# sb6pads.net
KiCad netlist of a schematic drawn in EAGLE
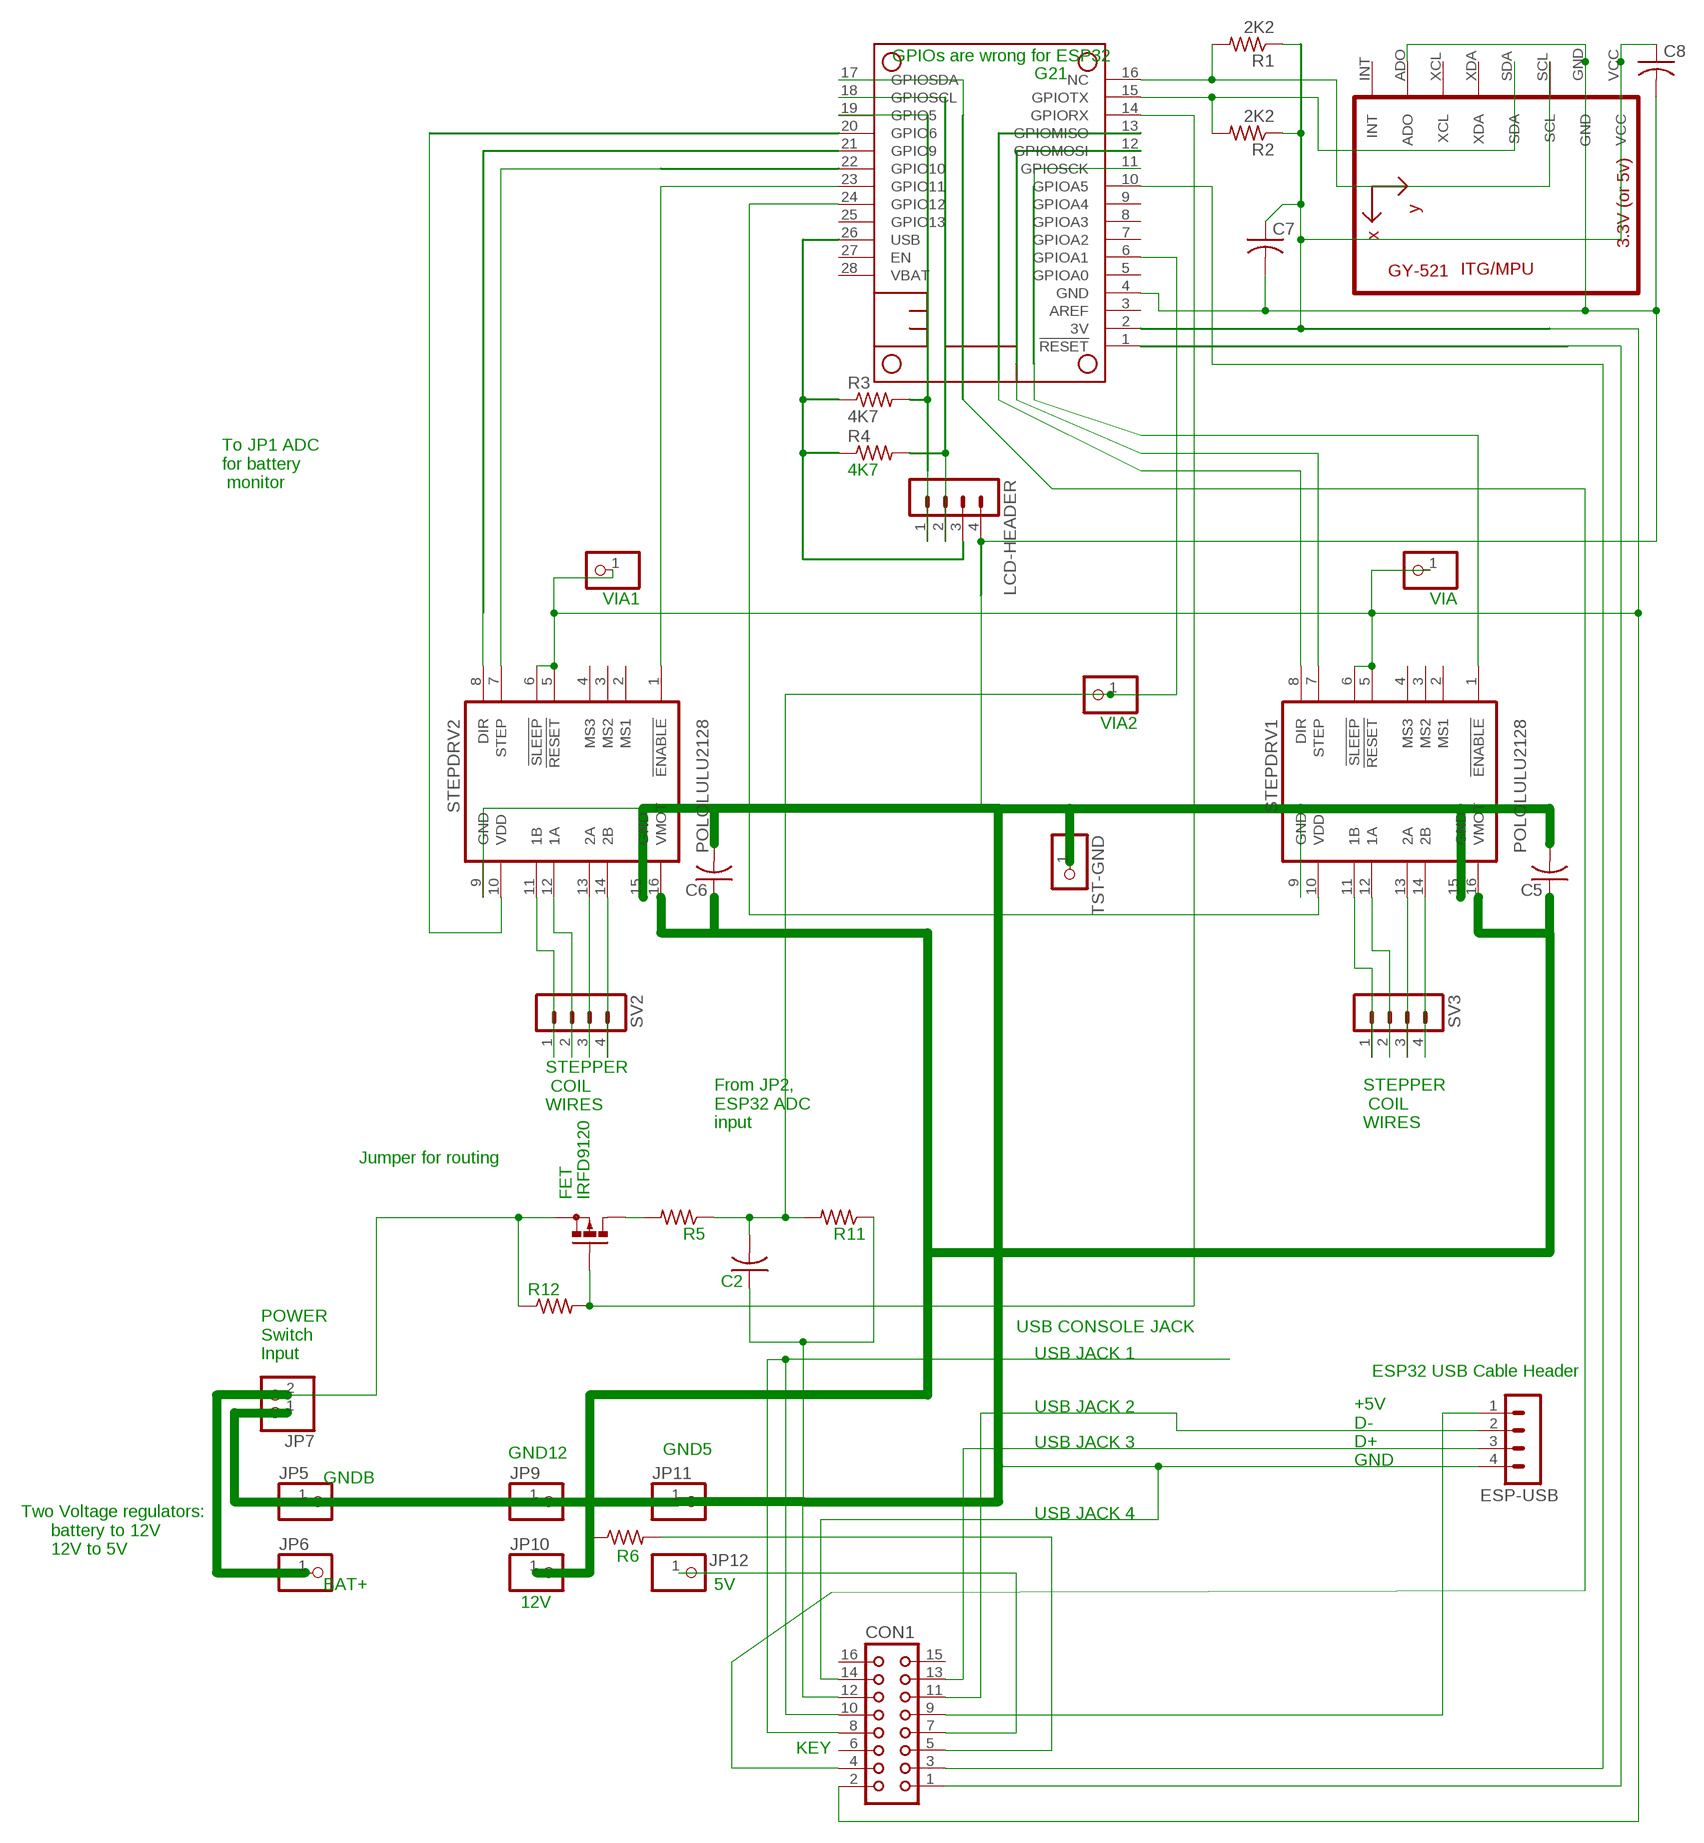
[diagram p0: schematic, sheet 1]

(export (version "E")
  (design (tool "Eeschema 10.0.6"))
  (components
    (comp (ref "C2")
      (value "C-US050-025X075")
      (footprint "eagle-import:C050-025X075")
      (libsource (lib "eagle-import") (part "C-US050-025X075"))
    )
    (comp (ref "C5")
      (value "C-US050-024X044")
      (footprint "eagle-import:C050-024X044")
      (libsource (lib "eagle-import") (part "C-US050-024X044"))
    )
    (comp (ref "C6")
      (value "C-US050-024X044")
      (footprint "eagle-import:C050-024X044")
      (libsource (lib "eagle-import") (part "C-US050-024X044"))
    )
    (comp (ref "C7")
      (value "C-US050-024X044")
      (footprint "eagle-import:C050-024X044")
      (libsource (lib "eagle-import") (part "C-US050-024X044"))
    )
    (comp (ref "C8")
      (value "C-US050-024X044")
      (footprint "eagle-import:C050-024X044")
      (libsource (lib "eagle-import") (part "C-US050-024X044"))
    )
    (comp (ref "CON1")
      (value "CON16")
      (footprint "eagle-import:CON16")
      (libsource (lib "eagle-import") (part "CON16"))
    )
    (comp (ref "ESP-USB")
      (value "MA04-1")
      (footprint "eagle-import:MA04-1")
      (libsource (lib "eagle-import") (part "MA04-1"))
    )
    (comp (ref "FET")
      (value "IRFD9120")
      (footprint "eagle-import:C370-01")
      (libsource (lib "eagle-import") (part "IRFD9120"))
    )
    (comp (ref "JP5")
      (value "PINHD-1X1")
      (footprint "eagle-import:1X01")
      (libsource (lib "eagle-import") (part "PINHD-1X1"))
    )
    (comp (ref "JP6")
      (value "PINHD-1X1")
      (footprint "eagle-import:1X01")
      (libsource (lib "eagle-import") (part "PINHD-1X1"))
    )
    (comp (ref "JP7")
      (value "PINHD-1X2")
      (footprint "eagle-import:1X02")
      (libsource (lib "eagle-import") (part "PINHD-1X2"))
    )
    (comp (ref "JP9")
      (value "PINHD-1X1")
      (footprint "eagle-import:1X01")
      (libsource (lib "eagle-import") (part "PINHD-1X1"))
    )
    (comp (ref "JP10")
      (value "PINHD-1X1")
      (footprint "eagle-import:1X01")
      (libsource (lib "eagle-import") (part "PINHD-1X1"))
    )
    (comp (ref "JP11")
      (value "PINHD-1X1")
      (footprint "eagle-import:1X01")
      (libsource (lib "eagle-import") (part "PINHD-1X1"))
    )
    (comp (ref "JP12")
      (value "PINHD-1X1")
      (footprint "eagle-import:1X01")
      (libsource (lib "eagle-import") (part "PINHD-1X1"))
    )
    (comp (ref "LCD-HEADER")
      (value "MA04-1")
      (footprint "eagle-import:MA04-1")
      (libsource (lib "eagle-import") (part "MA04-1"))
    )
    (comp (ref "MS2")
      (value "FEATHERWING_NOHOLES")
      (footprint "eagle-import:FEATHERWING_NOHOLES")
      (libsource (lib "eagle-import") (part "FEATHERWING_NOHOLES"))
    )
    (comp (ref "R1")
      (value "2K2")
      (footprint "eagle-import:0309_12")
      (libsource (lib "eagle-import") (part "resistor_348_R-US_0309/12"))
    )
    (comp (ref "R2")
      (value "2K2")
      (footprint "eagle-import:0309_12")
      (libsource (lib "eagle-import") (part "resistor_348_R-US_0309/12"))
    )
    (comp (ref "R3")
      (value "4K7")
      (footprint "eagle-import:0309_12")
      (libsource (lib "eagle-import") (part "resistor_348_R-US_0309/12"))
    )
    (comp (ref "R4")
      (value "4K7")
      (footprint "eagle-import:0309_12")
      (libsource (lib "eagle-import") (part "resistor_348_R-US_0309/12"))
    )
    (comp (ref "R5")
      (value "R-US_0207/10")
      (footprint "eagle-import:0207_10")
      (libsource (lib "eagle-import") (part "R-US_0207/10"))
    )
    (comp (ref "R6")
      (value "R-US_0207/10")
      (footprint "eagle-import:0207_10")
      (libsource (lib "eagle-import") (part "R-US_0207/10"))
    )
    (comp (ref "R11")
      (value "R-US_0207/10")
      (footprint "eagle-import:0207_10")
      (libsource (lib "eagle-import") (part "R-US_0207/10"))
    )
    (comp (ref "R12")
      (value "R-US_0207/10")
      (footprint "eagle-import:0207_10")
      (libsource (lib "eagle-import") (part "R-US_0207/10"))
    )
    (comp (ref "STEPDRV1")
      (value "POLOLULU2128")
      (footprint "eagle-import:POLOLULU2128")
      (libsource (lib "eagle-import") (part "POLOLULU2128"))
    )
    (comp (ref "STEPDRV2")
      (value "POLOLULU2128")
      (footprint "eagle-import:POLOLULU2128")
      (libsource (lib "eagle-import") (part "POLOLULU2128"))
    )
    (comp (ref "SV2")
      (value "MA04-1")
      (footprint "eagle-import:MA04-1")
      (libsource (lib "eagle-import") (part "MA04-1"))
    )
    (comp (ref "SV3")
      (value "MA04-1")
      (footprint "eagle-import:MA04-1")
      (libsource (lib "eagle-import") (part "MA04-1"))
    )
    (comp (ref "TST-GND")
      (value "PINHD-1X1")
      (footprint "eagle-import:1X01")
      (libsource (lib "eagle-import") (part "PINHD-1X1"))
    )
    (comp (ref "U1")
      (value "GY-521MPU6050")
      (footprint "eagle-import:GY-521")
      (libsource (lib "eagle-import") (part "GY-521MPU6050"))
    )
    (comp (ref "VIA")
      (value "PINHD-1X1")
      (footprint "eagle-import:1X01")
      (libsource (lib "eagle-import") (part "PINHD-1X1"))
    )
    (comp (ref "VIA1")
      (value "PINHD-1X1")
      (footprint "eagle-import:1X01")
      (libsource (lib "eagle-import") (part "PINHD-1X1"))
    )
    (comp (ref "VIA2")
      (value "PINHD-1X1")
      (footprint "eagle-import:1X01")
      (libsource (lib "eagle-import") (part "PINHD-1X1"))
    )
  )
  (nets
    (net (code "1") (name "/VBAT") (class "Default")
      (node (ref "MS2") (pin "28") (pinfunction "VBAT_28") (pintype "power_in"))
    )
    (net (code "2") (name "Net-(CON1-Pad5)") (class "Default")
      (node (ref "CON1") (pin "5") (pinfunction "5_5") (pintype "passive"))
      (node (ref "R6") (pin "2") (pinfunction "2_2") (pintype "passive"))
    )
    (net (code "3") (name "Net-(CON1-Pad7)") (class "Default")
      (node (ref "CON1") (pin "7") (pinfunction "7_7") (pintype "passive"))
      (node (ref "JP12") (pin "1") (pinfunction "1_1") (pintype "passive"))
    )
    (net (code "4") (name "Net-(CON1-Pad9)") (class "Default")
      (node (ref "CON1") (pin "9") (pinfunction "9_9") (pintype "passive"))
      (node (ref "ESP-USB") (pin "1") (pinfunction "1_1") (pintype "passive"))
    )
    (net (code "5") (name "Net-(CON1-Pad10)") (class "Default")
      (node (ref "CON1") (pin "10") (pinfunction "10_10") (pintype "passive"))
      (node (ref "CON1") (pin "8") (pinfunction "8_8") (pintype "passive"))
    )
    (net (code "6") (name "Net-(CON1-Pad11)") (class "Default")
      (node (ref "CON1") (pin "11") (pinfunction "11_11") (pintype "passive"))
      (node (ref "ESP-USB") (pin "2") (pinfunction "2_2") (pintype "passive"))
    )
    (net (code "7") (name "Net-(CON1-Pad13)") (class "Default")
      (node (ref "CON1") (pin "13") (pinfunction "13_13") (pintype "passive"))
      (node (ref "ESP-USB") (pin "3") (pinfunction "3_3") (pintype "passive"))
    )
    (net (code "8") (name "Net-(FET-D-PadD1)") (class "Default")
      (node (ref "FET") (pin "D") (pinfunction "D_D") (pintype "passive"))
      (node (ref "FET") (pin "D1") (pinfunction "D_D1") (pintype "passive"))
      (node (ref "R5") (pin "2") (pinfunction "2_2") (pintype "passive"))
    )
    (net (code "9") (name "Net-(FET-PadS)") (class "Default")
      (node (ref "FET") (pin "S") (pinfunction "S_S") (pintype "passive"))
      (node (ref "JP6") (pin "1") (pinfunction "1_1") (pintype "passive"))
      (node (ref "JP7") (pin "2") (pinfunction "2_2") (pintype "passive"))
      (node (ref "R12") (pin "1") (pinfunction "1_1") (pintype "passive"))
    )
    (net (code "10") (name "Net-(MS2-3V)") (class "Default")
      (node (ref "C7") (pin "1") (pinfunction "1_1") (pintype "passive"))
      (node (ref "C8") (pin "1") (pinfunction "1_1") (pintype "passive"))
      (node (ref "CON1") (pin "2") (pinfunction "2_2") (pintype "passive"))
      (node (ref "MS2") (pin "2") (pinfunction "3V_2") (pintype "power_in"))
      (node (ref "R1") (pin "1") (pinfunction "1_1") (pintype "passive"))
      (node (ref "R2") (pin "1") (pinfunction "1_1") (pintype "passive"))
      (node (ref "STEPDRV1") (pin "5") (pinfunction "~{RESET}_5") (pintype "input"))
      (node (ref "STEPDRV1") (pin "6") (pinfunction "~{SLEEP}_6") (pintype "input"))
      (node (ref "STEPDRV2") (pin "5") (pinfunction "~{RESET}_5") (pintype "input"))
      (node (ref "STEPDRV2") (pin "6") (pinfunction "~{SLEEP}_6") (pintype "input"))
      (node (ref "U1") (pin "VCC") (pinfunction "VCC_VCC") (pintype "bidirectional"))
      (node (ref "VIA") (pin "1") (pinfunction "1_1") (pintype "passive"))
      (node (ref "VIA1") (pin "1") (pinfunction "1_1") (pintype "passive"))
    )
    (net (code "11") (name "Net-(MS2-GND)") (class "Default")
      (node (ref "C2") (pin "1") (pinfunction "1_1") (pintype "passive"))
      (node (ref "C5") (pin "2") (pinfunction "2_2") (pintype "passive"))
      (node (ref "C6") (pin "2") (pinfunction "2_2") (pintype "passive"))
      (node (ref "C7") (pin "2") (pinfunction "2_2") (pintype "passive"))
      (node (ref "C8") (pin "2") (pinfunction "2_2") (pintype "passive"))
      (node (ref "CON1") (pin "12") (pinfunction "12_12") (pintype "passive"))
      (node (ref "CON1") (pin "14") (pinfunction "14_14") (pintype "passive"))
      (node (ref "ESP-USB") (pin "4") (pinfunction "4_4") (pintype "passive"))
      (node (ref "JP11") (pin "1") (pinfunction "1_1") (pintype "passive"))
      (node (ref "JP5") (pin "1") (pinfunction "1_1") (pintype "passive"))
      (node (ref "JP7") (pin "1") (pinfunction "1_1") (pintype "passive"))
      (node (ref "JP9") (pin "1") (pinfunction "1_1") (pintype "passive"))
      (node (ref "LCD-HEADER") (pin "4") (pinfunction "4_4") (pintype "passive"))
      (node (ref "MS2") (pin "4") (pinfunction "GND_4") (pintype "power_in"))
      (node (ref "R11") (pin "1") (pinfunction "1_1") (pintype "passive"))
      (node (ref "STEPDRV1") (pin "15") (pinfunction "GND_15") (pintype "power_in"))
      (node (ref "STEPDRV1") (pin "9") (pinfunction "GND_9") (pintype "power_in"))
      (node (ref "STEPDRV2") (pin "15") (pinfunction "GND_15") (pintype "power_in"))
      (node (ref "STEPDRV2") (pin "9") (pinfunction "GND_9") (pintype "power_in"))
      (node (ref "TST-GND") (pin "1") (pinfunction "1_1") (pintype "passive"))
      (node (ref "U1") (pin "ADO") (pinfunction "ADO_ADO") (pintype "bidirectional"))
      (node (ref "U1") (pin "GND") (pinfunction "GND_GND") (pintype "bidirectional"))
    )
    (net (code "12") (name "Net-(MS2-GPIO5)") (class "Default")
      (node (ref "LCD-HEADER") (pin "1") (pinfunction "1_1") (pintype "passive"))
      (node (ref "MS2") (pin "19") (pinfunction "GPIO5_19") (pintype "bidirectional"))
      (node (ref "R3") (pin "2") (pinfunction "2_2") (pintype "passive"))
    )
    (net (code "13") (name "Net-(MS2-GPIO6)") (class "Default")
      (node (ref "MS2") (pin "20") (pinfunction "GPIO6_20") (pintype "bidirectional"))
      (node (ref "STEPDRV2") (pin "10") (pinfunction "VDD_10") (pintype "power_in"))
    )
    (net (code "14") (name "Net-(MS2-GPIO9)") (class "Default")
      (node (ref "MS2") (pin "21") (pinfunction "GPIO9_21") (pintype "bidirectional"))
      (node (ref "STEPDRV2") (pin "8") (pinfunction "DIR_8") (pintype "input"))
    )
    (net (code "15") (name "Net-(MS2-GPIO10)") (class "Default")
      (node (ref "MS2") (pin "22") (pinfunction "GPIO10_22") (pintype "bidirectional"))
      (node (ref "STEPDRV2") (pin "7") (pinfunction "STEP_7") (pintype "input"))
    )
    (net (code "16") (name "Net-(MS2-GPIO11)") (class "Default")
      (node (ref "MS2") (pin "23") (pinfunction "GPIO11_23") (pintype "bidirectional"))
      (node (ref "STEPDRV2") (pin "1") (pinfunction "~{ENABLE}_1") (pintype "input"))
    )
    (net (code "17") (name "Net-(MS2-GPIO12)") (class "Default")
      (node (ref "MS2") (pin "24") (pinfunction "GPIO12_24") (pintype "bidirectional"))
      (node (ref "STEPDRV1") (pin "10") (pinfunction "VDD_10") (pintype "power_in"))
    )
    (net (code "18") (name "Net-(MS2-GPIOA1)") (class "Default")
      (node (ref "C2") (pin "2") (pinfunction "2_2") (pintype "passive"))
      (node (ref "MS2") (pin "6") (pinfunction "GPIOA1_6") (pintype "bidirectional"))
      (node (ref "R11") (pin "2") (pinfunction "2_2") (pintype "passive"))
      (node (ref "R5") (pin "1") (pinfunction "1_1") (pintype "passive"))
      (node (ref "VIA2") (pin "1") (pinfunction "1_1") (pintype "passive"))
    )
    (net (code "19") (name "Net-(MS2-GPIOA5)") (class "Default")
      (node (ref "CON1") (pin "3") (pinfunction "3_3") (pintype "passive"))
      (node (ref "MS2") (pin "10") (pinfunction "GPIOA5_10") (pintype "bidirectional"))
    )
    (net (code "20") (name "Net-(MS2-GPIOMISO)") (class "Default")
      (node (ref "MS2") (pin "13") (pinfunction "GPIOMISO_13") (pintype "bidirectional"))
      (node (ref "STEPDRV1") (pin "8") (pinfunction "DIR_8") (pintype "input"))
    )
    (net (code "21") (name "Net-(MS2-GPIOMOSI)") (class "Default")
      (node (ref "MS2") (pin "12") (pinfunction "GPIOMOSI_12") (pintype "bidirectional"))
      (node (ref "STEPDRV1") (pin "7") (pinfunction "STEP_7") (pintype "input"))
    )
    (net (code "22") (name "Net-(MS2-GPIORX)") (class "Default")
      (node (ref "FET") (pin "G") (pinfunction "G_G") (pintype "passive"))
      (node (ref "MS2") (pin "14") (pinfunction "GPIORX_14") (pintype "bidirectional"))
      (node (ref "R12") (pin "2") (pinfunction "2_2") (pintype "passive"))
    )
    (net (code "23") (name "Net-(MS2-GPIOSCK)") (class "Default")
      (node (ref "MS2") (pin "11") (pinfunction "GPIOSCK_11") (pintype "bidirectional"))
      (node (ref "STEPDRV1") (pin "1") (pinfunction "~{ENABLE}_1") (pintype "input"))
    )
    (net (code "24") (name "Net-(MS2-GPIOSCL)") (class "Default")
      (node (ref "LCD-HEADER") (pin "2") (pinfunction "2_2") (pintype "passive"))
      (node (ref "MS2") (pin "18") (pinfunction "GPIOSCL_18") (pintype "bidirectional"))
      (node (ref "R4") (pin "2") (pinfunction "2_2") (pintype "passive"))
    )
    (net (code "25") (name "Net-(MS2-GPIOSDA)") (class "Default")
      (node (ref "CON1") (pin "4") (pinfunction "4_4") (pintype "passive"))
      (node (ref "MS2") (pin "17") (pinfunction "GPIOSDA_17") (pintype "bidirectional"))
    )
    (net (code "26") (name "Net-(MS2-GPIOTX)") (class "Default")
      (node (ref "MS2") (pin "15") (pinfunction "GPIOTX_15") (pintype "bidirectional"))
      (node (ref "R2") (pin "2") (pinfunction "2_2") (pintype "passive"))
      (node (ref "U1") (pin "SDA") (pinfunction "SDA_SDA") (pintype "bidirectional"))
    )
    (net (code "27") (name "Net-(MS2-NC)") (class "Default")
      (node (ref "MS2") (pin "16") (pinfunction "NC_16") (pintype "passive"))
      (node (ref "R1") (pin "2") (pinfunction "2_2") (pintype "passive"))
      (node (ref "U1") (pin "SCL") (pinfunction "SCL_SCL") (pintype "bidirectional"))
    )
    (net (code "28") (name "Net-(MS2-USB)") (class "Default")
      (node (ref "LCD-HEADER") (pin "3") (pinfunction "3_3") (pintype "passive"))
      (node (ref "MS2") (pin "26") (pinfunction "USB_26") (pintype "power_in"))
      (node (ref "R3") (pin "1") (pinfunction "1_1") (pintype "passive"))
      (node (ref "R4") (pin "1") (pinfunction "1_1") (pintype "passive"))
    )
    (net (code "29") (name "Net-(MS2-~{RESET})") (class "Default")
      (node (ref "CON1") (pin "1") (pinfunction "1_1") (pintype "passive"))
      (node (ref "MS2") (pin "1") (pinfunction "~{RESET}_1") (pintype "input"))
    )
    (net (code "30") (name "Net-(STEPDRV1-1A)") (class "Default")
      (node (ref "STEPDRV1") (pin "12") (pinfunction "1A_12") (pintype "output"))
      (node (ref "SV3") (pin "2") (pinfunction "2_2") (pintype "passive"))
    )
    (net (code "31") (name "Net-(STEPDRV1-1B)") (class "Default")
      (node (ref "STEPDRV1") (pin "11") (pinfunction "1B_11") (pintype "output"))
      (node (ref "SV3") (pin "1") (pinfunction "1_1") (pintype "passive"))
    )
    (net (code "32") (name "Net-(STEPDRV1-2A)") (class "Default")
      (node (ref "STEPDRV1") (pin "13") (pinfunction "2A_13") (pintype "output"))
      (node (ref "SV3") (pin "3") (pinfunction "3_3") (pintype "passive"))
    )
    (net (code "33") (name "Net-(STEPDRV1-2B)") (class "Default")
      (node (ref "STEPDRV1") (pin "14") (pinfunction "2B_14") (pintype "output"))
      (node (ref "SV3") (pin "4") (pinfunction "4_4") (pintype "passive"))
    )
    (net (code "34") (name "Net-(STEPDRV1-VMOT)") (class "Default")
      (node (ref "C5") (pin "1") (pinfunction "1_1") (pintype "passive"))
      (node (ref "C6") (pin "1") (pinfunction "1_1") (pintype "passive"))
      (node (ref "JP10") (pin "1") (pinfunction "1_1") (pintype "passive"))
      (node (ref "R6") (pin "1") (pinfunction "1_1") (pintype "passive"))
      (node (ref "STEPDRV1") (pin "16") (pinfunction "VMOT_16") (pintype "power_in"))
      (node (ref "STEPDRV2") (pin "16") (pinfunction "VMOT_16") (pintype "power_in"))
    )
    (net (code "35") (name "Net-(STEPDRV2-1A)") (class "Default")
      (node (ref "STEPDRV2") (pin "12") (pinfunction "1A_12") (pintype "output"))
      (node (ref "SV2") (pin "2") (pinfunction "2_2") (pintype "passive"))
    )
    (net (code "36") (name "Net-(STEPDRV2-1B)") (class "Default")
      (node (ref "STEPDRV2") (pin "11") (pinfunction "1B_11") (pintype "output"))
      (node (ref "SV2") (pin "1") (pinfunction "1_1") (pintype "passive"))
    )
    (net (code "37") (name "Net-(STEPDRV2-2A)") (class "Default")
      (node (ref "STEPDRV2") (pin "13") (pinfunction "2A_13") (pintype "output"))
      (node (ref "SV2") (pin "3") (pinfunction "3_3") (pintype "passive"))
    )
    (net (code "38") (name "Net-(STEPDRV2-2B)") (class "Default")
      (node (ref "STEPDRV2") (pin "14") (pinfunction "2B_14") (pintype "output"))
      (node (ref "SV2") (pin "4") (pinfunction "4_4") (pintype "passive"))
    )
    (net (code "39") (name "unconnected-(CON1-Pad6)") (class "Default")
      (node (ref "CON1") (pin "6") (pinfunction "6_6") (pintype "passive"))
    )
    (net (code "40") (name "unconnected-(CON1-Pad15)") (class "Default")
      (node (ref "CON1") (pin "15") (pinfunction "15_15") (pintype "passive"))
    )
    (net (code "41") (name "unconnected-(CON1-Pad16)") (class "Default")
      (node (ref "CON1") (pin "16") (pinfunction "16_16") (pintype "passive"))
    )
    (net (code "42") (name "unconnected-(MS2-AREF-Pad3)") (class "Default")
      (node (ref "MS2") (pin "3") (pinfunction "AREF_3") (pintype "passive"))
    )
    (net (code "43") (name "unconnected-(MS2-EN-Pad27)") (class "Default")
      (node (ref "MS2") (pin "27") (pinfunction "EN_27") (pintype "passive"))
    )
    (net (code "44") (name "unconnected-(MS2-GPIO13-Pad25)") (class "Default")
      (node (ref "MS2") (pin "25") (pinfunction "GPIO13_25") (pintype "bidirectional"))
    )
    (net (code "45") (name "unconnected-(MS2-GPIOA0-Pad5)") (class "Default")
      (node (ref "MS2") (pin "5") (pinfunction "GPIOA0_5") (pintype "bidirectional"))
    )
    (net (code "46") (name "unconnected-(MS2-GPIOA2-Pad7)") (class "Default")
      (node (ref "MS2") (pin "7") (pinfunction "GPIOA2_7") (pintype "bidirectional"))
    )
    (net (code "47") (name "unconnected-(MS2-GPIOA3-Pad8)") (class "Default")
      (node (ref "MS2") (pin "8") (pinfunction "GPIOA3_8") (pintype "bidirectional"))
    )
    (net (code "48") (name "unconnected-(MS2-GPIOA4-Pad9)") (class "Default")
      (node (ref "MS2") (pin "9") (pinfunction "GPIOA4_9") (pintype "bidirectional"))
    )
    (net (code "49") (name "unconnected-(STEPDRV1-MS1-Pad2)") (class "Default")
      (node (ref "STEPDRV1") (pin "2") (pinfunction "MS1_2") (pintype "input"))
    )
    (net (code "50") (name "unconnected-(STEPDRV1-MS2-Pad3)") (class "Default")
      (node (ref "STEPDRV1") (pin "3") (pinfunction "MS2_3") (pintype "input"))
    )
    (net (code "51") (name "unconnected-(STEPDRV1-MS3-Pad4)") (class "Default")
      (node (ref "STEPDRV1") (pin "4") (pinfunction "MS3_4") (pintype "input"))
    )
    (net (code "52") (name "unconnected-(STEPDRV2-MS1-Pad2)") (class "Default")
      (node (ref "STEPDRV2") (pin "2") (pinfunction "MS1_2") (pintype "input"))
    )
    (net (code "53") (name "unconnected-(STEPDRV2-MS2-Pad3)") (class "Default")
      (node (ref "STEPDRV2") (pin "3") (pinfunction "MS2_3") (pintype "input"))
    )
    (net (code "54") (name "unconnected-(STEPDRV2-MS3-Pad4)") (class "Default")
      (node (ref "STEPDRV2") (pin "4") (pinfunction "MS3_4") (pintype "input"))
    )
    (net (code "55") (name "unconnected-(U1-PadINT)") (class "Default")
      (node (ref "U1") (pin "INT") (pinfunction "INT_INT") (pintype "bidirectional"))
    )
    (net (code "56") (name "unconnected-(U1-PadXCL)") (class "Default")
      (node (ref "U1") (pin "XCL") (pinfunction "XCL_XCL") (pintype "bidirectional"))
    )
    (net (code "57") (name "unconnected-(U1-PadXDA)") (class "Default")
      (node (ref "U1") (pin "XDA") (pinfunction "XDA_XDA") (pintype "bidirectional"))
    )
  )
)
